# mfrhp.net
KiCad netlist of a schematic drawn in EAGLE
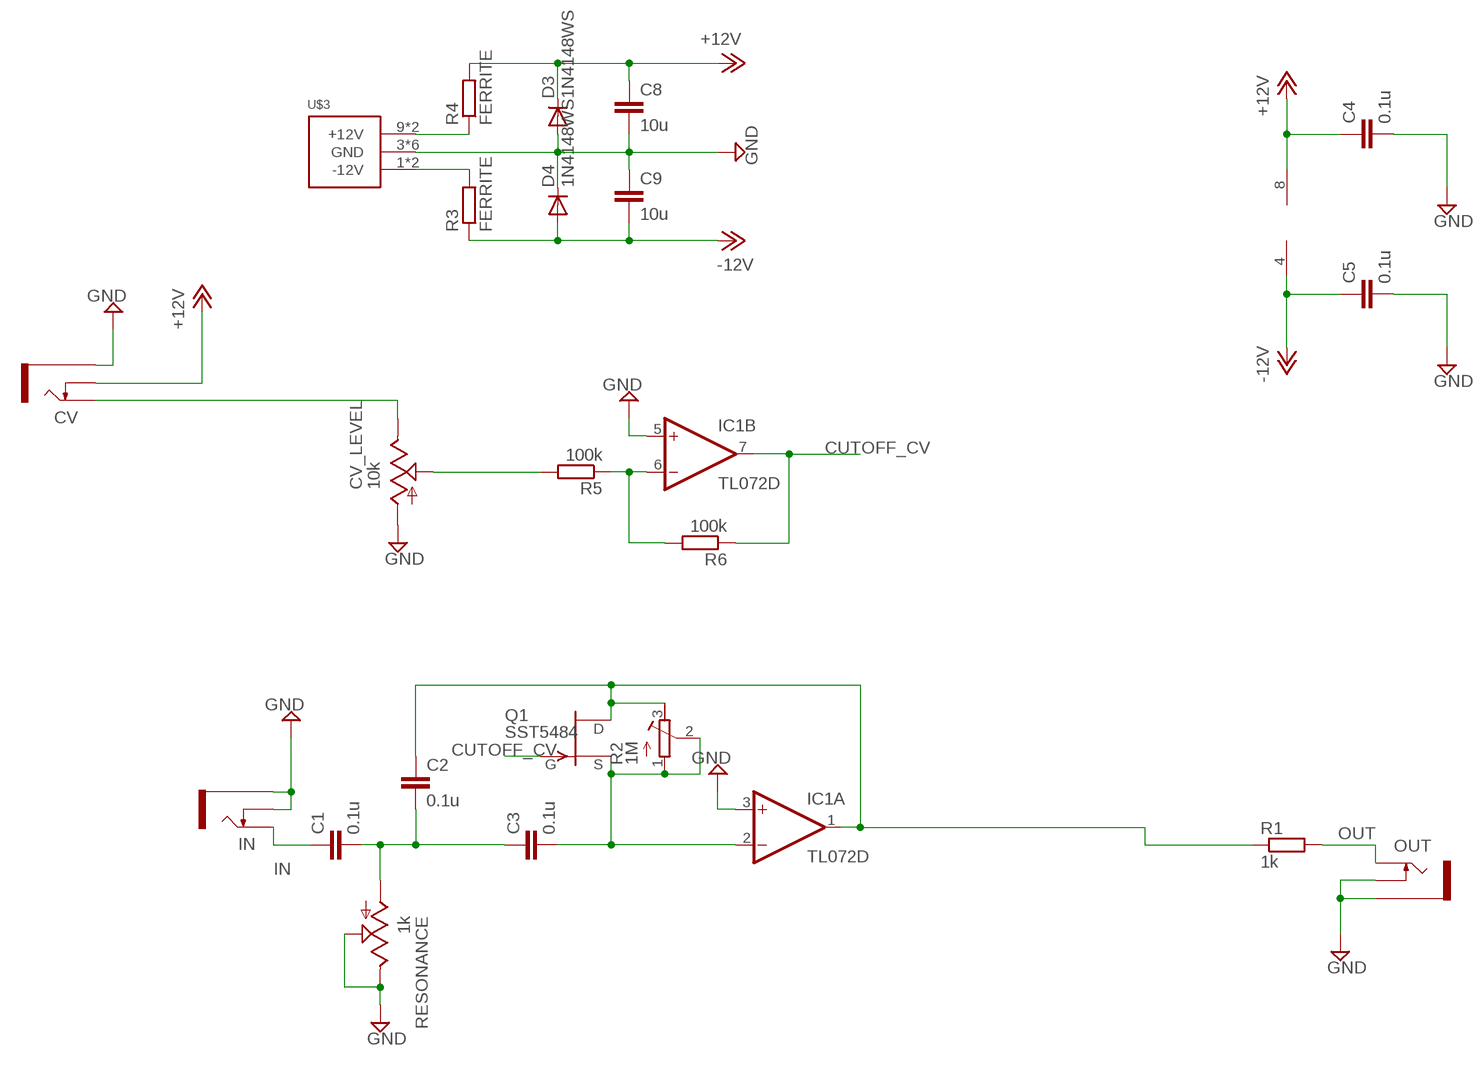
[diagram p0: schematic, sheet 1]

(export (version "E")
  (design (tool "Eeschema 10.0.6"))
  (components
    (comp (ref "C1")
      (value "0.1u")
      (footprint "eagle-import:C0805")
      (libsource (lib "eagle-import") (part "C-EUC0805"))
    )
    (comp (ref "C2")
      (value "0.1u")
      (footprint "eagle-import:C0805")
      (libsource (lib "eagle-import") (part "C-EUC0805"))
    )
    (comp (ref "C3")
      (value "0.1u")
      (footprint "eagle-import:C0805")
      (libsource (lib "eagle-import") (part "C-EUC0805"))
    )
    (comp (ref "C4")
      (value "0.1u")
      (footprint "eagle-import:C0805")
      (libsource (lib "eagle-import") (part "C-EUC0805"))
    )
    (comp (ref "C5")
      (value "0.1u")
      (footprint "eagle-import:C0805")
      (libsource (lib "eagle-import") (part "C-EUC0805"))
    )
    (comp (ref "C8")
      (value "10u")
      (footprint "eagle-import:C0805")
      (libsource (lib "eagle-import") (part "C-EUC0805"))
    )
    (comp (ref "C9")
      (value "10u")
      (footprint "eagle-import:C0805")
      (libsource (lib "eagle-import") (part "C-EUC0805"))
    )
    (comp (ref "CV")
      (value "THONKICONNNEW")
      (footprint "eagle-import:WQP-PJ301M-12_JACK")
      (libsource (lib "eagle-import") (part "THONKICONNNEW"))
    )
    (comp (ref "CV_LEVEL")
      (value "10k")
      (footprint "eagle-import:9MM_SNAP-IN_POT")
      (libsource (lib "eagle-import") (part "9MM_SNAP-IN_POT_"))
    )
    (comp (ref "D3")
      (value "1N4148WS")
      (footprint "eagle-import:SOD323-W")
      (libsource (lib "eagle-import") (part "DIODE-SOD323-W"))
    )
    (comp (ref "D4")
      (value "1N4148WS")
      (footprint "eagle-import:SOD323-W")
      (libsource (lib "eagle-import") (part "DIODE-SOD323-W"))
    )
    (comp (ref "IC1")
      (value "TL072D")
      (footprint "eagle-import:SO08")
      (libsource (lib "eagle-import") (part "TL072D"))
    )
    (comp (ref "IN")
      (value "THONKICONNNEW")
      (footprint "eagle-import:WQP-PJ301M-12_JACK")
      (libsource (lib "eagle-import") (part "THONKICONNNEW"))
    )
    (comp (ref "OUT")
      (value "THONKICONNNEW")
      (footprint "eagle-import:WQP-PJ301M-12_JACK")
      (libsource (lib "eagle-import") (part "THONKICONNNEW"))
    )
    (comp (ref "Q1")
      (value "SST5484")
      (footprint "eagle-import:SOT23")
      (libsource (lib "eagle-import") (part "?548SST4"))
    )
    (comp (ref "R1")
      (value "1k")
      (footprint "eagle-import:R0805")
      (libsource (lib "eagle-import") (part "R-EU_R0805"))
    )
    (comp (ref "R2")
      (value "1M")
      (footprint "eagle-import:RTRIM3296W")
      (libsource (lib "eagle-import") (part "R-TRIMM3296W"))
    )
    (comp (ref "R3")
      (value "FERRITE")
      (footprint "eagle-import:R0805")
      (libsource (lib "eagle-import") (part "R-EU_R0805"))
    )
    (comp (ref "R4")
      (value "FERRITE")
      (footprint "eagle-import:R0805")
      (libsource (lib "eagle-import") (part "R-EU_R0805"))
    )
    (comp (ref "R5")
      (value "100k")
      (footprint "eagle-import:R0805")
      (libsource (lib "eagle-import") (part "R-EU_R0805"))
    )
    (comp (ref "R6")
      (value "100k")
      (footprint "eagle-import:R0805")
      (libsource (lib "eagle-import") (part "R-EU_R0805"))
    )
    (comp (ref "RESONANCE")
      (value "1k")
      (footprint "eagle-import:9MM_SNAP-IN_POT")
      (libsource (lib "eagle-import") (part "9MM_SNAP-IN_POT_"))
    )
    (comp (ref "U$3")
      (value "POWER_SIMPLE10")
      (footprint "eagle-import:POWER_10")
      (libsource (lib "eagle-import") (part "POWER_SIMPLE10"))
    )
  )
  (nets
    (net (code "1") (name "+12V") (class "Default")
      (node (ref "C4") (pin "1") (pinfunction "1_1") (pintype "passive"))
      (node (ref "C8") (pin "1") (pinfunction "1_1") (pintype "passive"))
      (node (ref "CV") (pin "P$2_SWITCH") (pinfunction "SWITCH_P$2_SWITCH") (pintype "passive"))
      (node (ref "D3") (pin "C") (pinfunction "C_C") (pintype "passive"))
      (node (ref "IC1") (pin "8") (pinfunction "V+_8") (pintype "power_in"))
      (node (ref "R4") (pin "2") (pinfunction "2_2") (pintype "passive"))
    )
    (net (code "2") (name "-12V") (class "Default")
      (node (ref "C5") (pin "1") (pinfunction "1_1") (pintype "passive"))
      (node (ref "C9") (pin "2") (pinfunction "2_2") (pintype "passive"))
      (node (ref "D4") (pin "A") (pinfunction "A_A") (pintype "passive"))
      (node (ref "IC1") (pin "4") (pinfunction "V-_4") (pintype "power_in"))
      (node (ref "R3") (pin "1") (pinfunction "1_1") (pintype "passive"))
    )
    (net (code "3") (name "/CUTOFF_CV") (class "Default")
      (node (ref "IC1") (pin "7") (pinfunction "OUT_7") (pintype "output"))
      (node (ref "Q1") (pin "3") (pinfunction "G_3") (pintype "passive"))
      (node (ref "R6") (pin "1") (pinfunction "1_1") (pintype "passive"))
    )
    (net (code "4") (name "/IN") (class "Default")
      (node (ref "C1") (pin "1") (pinfunction "1_1") (pintype "passive"))
      (node (ref "IN") (pin "P$1_TIP") (pinfunction "TIP_P$1_TIP") (pintype "passive"))
    )
    (net (code "5") (name "/OUT") (class "Default")
      (node (ref "OUT") (pin "P$1_TIP") (pinfunction "TIP_P$1_TIP") (pintype "passive"))
      (node (ref "R1") (pin "2") (pinfunction "2_2") (pintype "passive"))
    )
    (net (code "6") (name "GND") (class "Default")
      (node (ref "C4") (pin "2") (pinfunction "2_2") (pintype "passive"))
      (node (ref "C5") (pin "2") (pinfunction "2_2") (pintype "passive"))
      (node (ref "C8") (pin "2") (pinfunction "2_2") (pintype "passive"))
      (node (ref "C9") (pin "1") (pinfunction "1_1") (pintype "passive"))
      (node (ref "CV") (pin "P$3_SLEEVE") (pinfunction "SLEEVE_P$3_SLEEVE") (pintype "passive"))
      (node (ref "CV_LEVEL") (pin "1") (pinfunction "A_1") (pintype "passive"))
      (node (ref "D3") (pin "A") (pinfunction "A_A") (pintype "passive"))
      (node (ref "D4") (pin "C") (pinfunction "C_C") (pintype "passive"))
      (node (ref "IC1") (pin "3") (pinfunction "+IN_3") (pintype "input"))
      (node (ref "IC1") (pin "5") (pinfunction "+IN_5") (pintype "input"))
      (node (ref "IN") (pin "P$2_SWITCH") (pinfunction "SWITCH_P$2_SWITCH") (pintype "passive"))
      (node (ref "IN") (pin "P$3_SLEEVE") (pinfunction "SLEEVE_P$3_SLEEVE") (pintype "passive"))
      (node (ref "OUT") (pin "P$2_SWITCH") (pinfunction "SWITCH_P$2_SWITCH") (pintype "passive"))
      (node (ref "OUT") (pin "P$3_SLEEVE") (pinfunction "SLEEVE_P$3_SLEEVE") (pintype "passive"))
      (node (ref "RESONANCE") (pin "2") (pinfunction "S_2") (pintype "passive"))
      (node (ref "RESONANCE") (pin "3") (pinfunction "E_3") (pintype "passive"))
      (node (ref "U$3") (pin "3") (pinfunction "GND_3") (pintype "bidirectional"))
      (node (ref "U$3") (pin "4") (pinfunction "GND_4") (pintype "bidirectional"))
      (node (ref "U$3") (pin "5") (pinfunction "GND_5") (pintype "bidirectional"))
      (node (ref "U$3") (pin "6") (pinfunction "GND_6") (pintype "bidirectional"))
      (node (ref "U$3") (pin "7") (pinfunction "GND_7") (pintype "bidirectional"))
      (node (ref "U$3") (pin "8") (pinfunction "GND_8") (pintype "bidirectional"))
    )
    (net (code "7") (name "Net-(CV-TIP)") (class "Default")
      (node (ref "CV") (pin "P$1_TIP") (pinfunction "TIP_P$1_TIP") (pintype "passive"))
      (node (ref "CV_LEVEL") (pin "3") (pinfunction "E_3") (pintype "passive"))
    )
    (net (code "8") (name "Net-(CV_LEVEL-S)") (class "Default")
      (node (ref "CV_LEVEL") (pin "2") (pinfunction "S_2") (pintype "passive"))
      (node (ref "R5") (pin "2") (pinfunction "2_2") (pintype "passive"))
    )
    (net (code "9") (name "Net-(IC1A--IN)") (class "Default")
      (node (ref "C3") (pin "2") (pinfunction "2_2") (pintype "passive"))
      (node (ref "IC1") (pin "2") (pinfunction "-IN_2") (pintype "input"))
      (node (ref "Q1") (pin "2") (pinfunction "S_2") (pintype "passive"))
      (node (ref "R2") (pin "1") (pinfunction "A_1") (pintype "passive"))
      (node (ref "R2") (pin "2") (pinfunction "S_2") (pintype "passive"))
    )
    (net (code "10") (name "Net-(IC1A-OUT)") (class "Default")
      (node (ref "C2") (pin "1") (pinfunction "1_1") (pintype "passive"))
      (node (ref "IC1") (pin "1") (pinfunction "OUT_1") (pintype "output"))
      (node (ref "Q1") (pin "1") (pinfunction "D_1") (pintype "passive"))
      (node (ref "R1") (pin "1") (pinfunction "1_1") (pintype "passive"))
      (node (ref "R2") (pin "3") (pinfunction "E_3") (pintype "passive"))
    )
    (net (code "11") (name "Net-(IC1B--IN)") (class "Default")
      (node (ref "IC1") (pin "6") (pinfunction "-IN_6") (pintype "input"))
      (node (ref "R5") (pin "1") (pinfunction "1_1") (pintype "passive"))
      (node (ref "R6") (pin "2") (pinfunction "2_2") (pintype "passive"))
    )
    (net (code "12") (name "Net-(R3-Pad2)") (class "Default")
      (node (ref "R3") (pin "2") (pinfunction "2_2") (pintype "passive"))
      (node (ref "U$3") (pin "1") (pinfunction "-12V_1") (pintype "bidirectional"))
      (node (ref "U$3") (pin "2") (pinfunction "-12V_2") (pintype "bidirectional"))
    )
    (net (code "13") (name "Net-(R4-Pad1)") (class "Default")
      (node (ref "R4") (pin "1") (pinfunction "1_1") (pintype "passive"))
      (node (ref "U$3") (pin "10") (pinfunction "+12V_10") (pintype "bidirectional"))
      (node (ref "U$3") (pin "9") (pinfunction "+12V_9") (pintype "bidirectional"))
    )
    (net (code "14") (name "Net-(RESONANCE-A)") (class "Default")
      (node (ref "C1") (pin "2") (pinfunction "2_2") (pintype "passive"))
      (node (ref "C2") (pin "2") (pinfunction "2_2") (pintype "passive"))
      (node (ref "C3") (pin "1") (pinfunction "1_1") (pintype "passive"))
      (node (ref "RESONANCE") (pin "1") (pinfunction "A_1") (pintype "passive"))
    )
  )
)
